# 4port.net
KiCad netlist of a schematic drawn in EAGLE
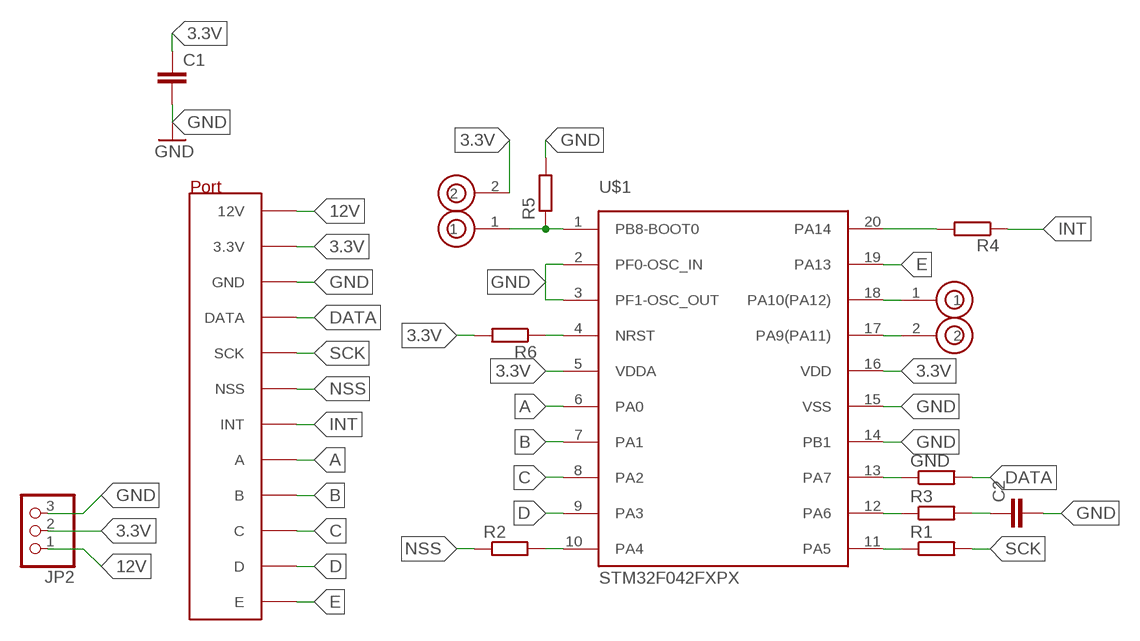
[diagram p0: schematic, sheet 1]

(export (version "E")
  (design (tool "Eeschema 10.0.6"))
  (components
    (comp (ref "C1")
      (value "C-EUC1206")
      (footprint "eagle-import:C1206")
      (libsource (lib "eagle-import") (part "C-EUC1206"))
    )
    (comp (ref "C2")
      (value "C-EUC1206")
      (footprint "eagle-import:C1206")
      (libsource (lib "eagle-import") (part "C-EUC1206"))
    )
    (comp (ref "GND")
      (value "R-EU_R0603")
      (footprint "eagle-import:R0603")
      (libsource (lib "eagle-import") (part "R-EU_R0603"))
    )
    (comp (ref "JP2")
      (value "PINHD-1X3")
      (footprint "eagle-import:1X03")
      (libsource (lib "eagle-import") (part "PINHD-1X3"))
    )
    (comp (ref "R1")
      (value "R-EU_R0603")
      (footprint "eagle-import:R0603")
      (libsource (lib "eagle-import") (part "R-EU_R0603"))
    )
    (comp (ref "R2")
      (value "R-EU_R0603")
      (footprint "eagle-import:R0603")
      (libsource (lib "eagle-import") (part "R-EU_R0603"))
    )
    (comp (ref "R3")
      (value "R-EU_R0603")
      (footprint "eagle-import:R0603")
      (libsource (lib "eagle-import") (part "R-EU_R0603"))
    )
    (comp (ref "R4")
      (value "R-EU_R0603")
      (footprint "eagle-import:R0603")
      (libsource (lib "eagle-import") (part "R-EU_R0603"))
    )
    (comp (ref "R5")
      (value "R-EU_R0603")
      (footprint "eagle-import:R0603")
      (libsource (lib "eagle-import") (part "R-EU_R0603"))
    )
    (comp (ref "R6")
      (value "R-EU_R0603")
      (footprint "eagle-import:R0603")
      (libsource (lib "eagle-import") (part "R-EU_R0603"))
    )
    (comp (ref "U$1")
      (value "STM32F042FXPX")
      (footprint "eagle-import:TSSOP20")
      (libsource (lib "eagle-import") (part "STM32F042FXPX"))
    )
    (comp (ref "U$2")
      (value "GOLDPIN_2")
      (footprint "eagle-import:GOLDPIN_2_SMD")
      (libsource (lib "eagle-import") (part "GOLDPIN_2"))
    )
    (comp (ref "U$3")
      (value "GOLDPIN_2")
      (footprint "eagle-import:GOLDPIN_2_SMD")
      (libsource (lib "eagle-import") (part "GOLDPIN_2"))
    )
    (comp (ref "U$4")
      (value "HUB_PORT")
      (footprint "eagle-import:HUB_PORT")
      (libsource (lib "eagle-import") (part "HUB_PORT"))
    )
  )
  (nets
    (net (code "1") (name "3.3V") (class "Default")
      (node (ref "C1") (pin "1") (pinfunction "1_1") (pintype "passive"))
      (node (ref "JP2") (pin "2") (pinfunction "2_2") (pintype "passive"))
      (node (ref "R6") (pin "2") (pinfunction "2_2") (pintype "passive"))
      (node (ref "U$1") (pin "16") (pinfunction "VDD_16") (pintype "bidirectional"))
      (node (ref "U$1") (pin "5") (pinfunction "VDDA_5") (pintype "bidirectional"))
      (node (ref "U$2") (pin "2") (pinfunction "2_2") (pintype "bidirectional"))
      (node (ref "U$4") (pin "3.3V") (pinfunction "3.3V_3.3V") (pintype "bidirectional"))
    )
    (net (code "2") (name "12V") (class "Default")
      (node (ref "JP2") (pin "1") (pinfunction "1_1") (pintype "passive"))
      (node (ref "U$4") (pin "12V") (pinfunction "12V_12V") (pintype "bidirectional"))
    )
    (net (code "3") (name "A") (class "Default")
      (node (ref "U$1") (pin "6") (pinfunction "PA0_6") (pintype "bidirectional"))
      (node (ref "U$4") (pin "A") (pinfunction "A_A") (pintype "bidirectional"))
    )
    (net (code "4") (name "B") (class "Default")
      (node (ref "U$1") (pin "7") (pinfunction "PA1_7") (pintype "bidirectional"))
      (node (ref "U$4") (pin "B") (pinfunction "B_B") (pintype "bidirectional"))
    )
    (net (code "5") (name "C") (class "Default")
      (node (ref "U$1") (pin "8") (pinfunction "PA2_8") (pintype "bidirectional"))
      (node (ref "U$4") (pin "C") (pinfunction "C_C") (pintype "bidirectional"))
    )
    (net (code "6") (name "D") (class "Default")
      (node (ref "U$1") (pin "9") (pinfunction "PA3_9") (pintype "bidirectional"))
      (node (ref "U$4") (pin "D") (pinfunction "D_D") (pintype "bidirectional"))
    )
    (net (code "7") (name "DATA") (class "Default")
      (node (ref "GND") (pin "2") (pinfunction "2_2") (pintype "passive"))
      (node (ref "U$4") (pin "DATA") (pinfunction "DATA_DATA") (pintype "bidirectional"))
    )
    (net (code "8") (name "E") (class "Default")
      (node (ref "U$1") (pin "19") (pinfunction "PA13_19") (pintype "bidirectional"))
      (node (ref "U$4") (pin "E") (pinfunction "E_E") (pintype "bidirectional"))
    )
    (net (code "9") (name "GND") (class "Default")
      (node (ref "C1") (pin "2") (pinfunction "2_2") (pintype "passive"))
      (node (ref "C2") (pin "2") (pinfunction "2_2") (pintype "passive"))
      (node (ref "JP2") (pin "3") (pinfunction "3_3") (pintype "passive"))
      (node (ref "R5") (pin "2") (pinfunction "2_2") (pintype "passive"))
      (node (ref "U$1") (pin "14") (pinfunction "PB1_14") (pintype "bidirectional"))
      (node (ref "U$1") (pin "15") (pinfunction "VSS_15") (pintype "bidirectional"))
      (node (ref "U$1") (pin "2") (pinfunction "PF0-OSC_IN_2") (pintype "bidirectional"))
      (node (ref "U$1") (pin "3") (pinfunction "PF1-OSC_OUT_3") (pintype "bidirectional"))
      (node (ref "U$4") (pin "GND") (pinfunction "GND_GND") (pintype "bidirectional"))
    )
    (net (code "10") (name "INT") (class "Default")
      (node (ref "R4") (pin "1") (pinfunction "1_1") (pintype "passive"))
      (node (ref "U$4") (pin "INT") (pinfunction "INT_INT") (pintype "bidirectional"))
    )
    (net (code "11") (name "NSS") (class "Default")
      (node (ref "R2") (pin "1") (pinfunction "1_1") (pintype "passive"))
      (node (ref "U$4") (pin "NSS") (pinfunction "NSS_NSS") (pintype "bidirectional"))
    )
    (net (code "12") (name "Net-(C2-Pad1)") (class "Default")
      (node (ref "C2") (pin "1") (pinfunction "1_1") (pintype "passive"))
      (node (ref "R3") (pin "2") (pinfunction "2_2") (pintype "passive"))
    )
    (net (code "13") (name "Net-(U$1-NRST)") (class "Default")
      (node (ref "R6") (pin "1") (pinfunction "1_1") (pintype "passive"))
      (node (ref "U$1") (pin "4") (pinfunction "NRST_4") (pintype "bidirectional"))
    )
    (net (code "14") (name "Net-(U$1-PA4)") (class "Default")
      (node (ref "R2") (pin "2") (pinfunction "2_2") (pintype "passive"))
      (node (ref "U$1") (pin "10") (pinfunction "PA4_10") (pintype "bidirectional"))
    )
    (net (code "15") (name "Net-(U$1-PA5)") (class "Default")
      (node (ref "R1") (pin "1") (pinfunction "1_1") (pintype "passive"))
      (node (ref "U$1") (pin "11") (pinfunction "PA5_11") (pintype "bidirectional"))
    )
    (net (code "16") (name "Net-(U$1-PA6)") (class "Default")
      (node (ref "R3") (pin "1") (pinfunction "1_1") (pintype "passive"))
      (node (ref "U$1") (pin "12") (pinfunction "PA6_12") (pintype "bidirectional"))
    )
    (net (code "17") (name "Net-(U$1-PA7)") (class "Default")
      (node (ref "GND") (pin "1") (pinfunction "1_1") (pintype "passive"))
      (node (ref "U$1") (pin "13") (pinfunction "PA7_13") (pintype "bidirectional"))
    )
    (net (code "18") (name "Net-(U$1-PA9(PA11))") (class "Default")
      (node (ref "U$1") (pin "17") (pinfunction "PA9(PA11)_17") (pintype "bidirectional"))
      (node (ref "U$3") (pin "2") (pinfunction "2_2") (pintype "bidirectional"))
    )
    (net (code "19") (name "Net-(U$1-PA10(PA12))") (class "Default")
      (node (ref "U$1") (pin "18") (pinfunction "PA10(PA12)_18") (pintype "bidirectional"))
      (node (ref "U$3") (pin "1") (pinfunction "1_1") (pintype "bidirectional"))
    )
    (net (code "20") (name "Net-(U$1-PA14)") (class "Default")
      (node (ref "R4") (pin "2") (pinfunction "2_2") (pintype "passive"))
      (node (ref "U$1") (pin "20") (pinfunction "PA14_20") (pintype "bidirectional"))
    )
    (net (code "21") (name "Net-(U$1-PB8-BOOT0)") (class "Default")
      (node (ref "R5") (pin "1") (pinfunction "1_1") (pintype "passive"))
      (node (ref "U$1") (pin "1") (pinfunction "PB8-BOOT0_1") (pintype "bidirectional"))
      (node (ref "U$2") (pin "1") (pinfunction "1_1") (pintype "bidirectional"))
    )
    (net (code "22") (name "SCK") (class "Default")
      (node (ref "R1") (pin "2") (pinfunction "2_2") (pintype "passive"))
      (node (ref "U$4") (pin "SCK") (pinfunction "SCK_SCK") (pintype "bidirectional"))
    )
  )
)
